# ASBB_Servo.net
KiCad netlist of a schematic drawn in Altium Designer
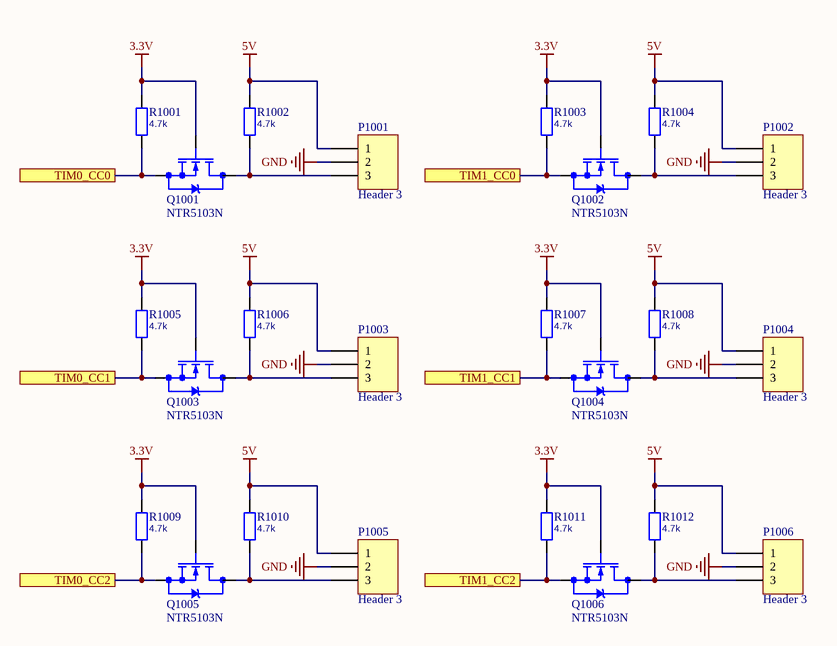
[diagram p0: ASBB_Servo.SchDoc]

(export (version "E")
  (design (tool "Eeschema 10.0.6"))
  (components
    (comp (ref "P1001")
      (value "Header 3")
      (footprint "HDR1X3")
      (description "Header, 3-Pin")
      (fields (field (name "PUBLISHER") "Altium Limited"))
      (libsource (lib "Miscellaneous Connectors") (part "Header 3"))
    )
    (comp (ref "P1002")
      (value "Header 3")
      (footprint "HDR1X3")
      (description "Header, 3-Pin")
      (fields (field (name "PUBLISHER") "Altium Limited"))
      (libsource (lib "Miscellaneous Connectors") (part "Header 3"))
    )
    (comp (ref "P1003")
      (value "Header 3")
      (footprint "HDR1X3")
      (description "Header, 3-Pin")
      (fields (field (name "PUBLISHER") "Altium Limited"))
      (libsource (lib "Miscellaneous Connectors") (part "Header 3"))
    )
    (comp (ref "P1004")
      (value "Header 3")
      (footprint "HDR1X3")
      (description "Header, 3-Pin")
      (fields (field (name "PUBLISHER") "Altium Limited"))
      (libsource (lib "Miscellaneous Connectors") (part "Header 3"))
    )
    (comp (ref "P1005")
      (value "Header 3")
      (footprint "HDR1X3")
      (description "Header, 3-Pin")
      (fields (field (name "PUBLISHER") "Altium Limited"))
      (libsource (lib "Miscellaneous Connectors") (part "Header 3"))
    )
    (comp (ref "P1006")
      (value "Header 3")
      (footprint "HDR1X3")
      (description "Header, 3-Pin")
      (fields (field (name "PUBLISHER") "Altium Limited"))
      (libsource (lib "Miscellaneous Connectors") (part "Header 3"))
    )
    (comp (ref "Q1001")
      (value "NTR5103N")
      (footprint "FZI:SOT23")
      (description "N-Channel MOSFET SOT23")
      (fields (field (name "PARTNUMBER") "?"))
      (libsource (lib "FZI") (part "NMOS SOT23"))
    )
    (comp (ref "Q1002")
      (value "NTR5103N")
      (footprint "FZI:SOT23")
      (description "N-Channel MOSFET SOT23")
      (fields (field (name "PARTNUMBER") "?"))
      (libsource (lib "FZI") (part "NMOS SOT23"))
    )
    (comp (ref "Q1003")
      (value "NTR5103N")
      (footprint "FZI:SOT23")
      (description "N-Channel MOSFET SOT23")
      (fields (field (name "PARTNUMBER") "?"))
      (libsource (lib "FZI") (part "NMOS SOT23"))
    )
    (comp (ref "Q1004")
      (value "NTR5103N")
      (footprint "FZI:SOT23")
      (description "N-Channel MOSFET SOT23")
      (fields (field (name "PARTNUMBER") "?"))
      (libsource (lib "FZI") (part "NMOS SOT23"))
    )
    (comp (ref "Q1005")
      (value "NTR5103N")
      (footprint "FZI:SOT23")
      (description "N-Channel MOSFET SOT23")
      (fields (field (name "PARTNUMBER") "?"))
      (libsource (lib "FZI") (part "NMOS SOT23"))
    )
    (comp (ref "Q1006")
      (value "NTR5103N")
      (footprint "FZI:SOT23")
      (description "N-Channel MOSFET SOT23")
      (fields (field (name "PARTNUMBER") "?"))
      (libsource (lib "FZI") (part "NMOS SOT23"))
    )
    (comp (ref "R1001")
      (value "4.7k")
      (footprint "0603")
      (description "Resistor")
      (fields (field (name "PARTNUMBER") "?"))
      (libsource (lib "FZI") (part "Resistor"))
    )
    (comp (ref "R1002")
      (value "4.7k")
      (footprint "0603")
      (description "Resistor")
      (fields (field (name "PARTNUMBER") "?"))
      (libsource (lib "FZI") (part "Resistor"))
    )
    (comp (ref "R1003")
      (value "4.7k")
      (footprint "0603")
      (description "Resistor")
      (fields (field (name "PARTNUMBER") "?"))
      (libsource (lib "FZI") (part "Resistor"))
    )
    (comp (ref "R1004")
      (value "4.7k")
      (footprint "0603")
      (description "Resistor")
      (fields (field (name "PARTNUMBER") "?"))
      (libsource (lib "FZI") (part "Resistor"))
    )
    (comp (ref "R1005")
      (value "4.7k")
      (footprint "0603")
      (description "Resistor")
      (fields (field (name "PARTNUMBER") "?"))
      (libsource (lib "FZI") (part "Resistor"))
    )
    (comp (ref "R1006")
      (value "4.7k")
      (footprint "0603")
      (description "Resistor")
      (fields (field (name "PARTNUMBER") "?"))
      (libsource (lib "FZI") (part "Resistor"))
    )
    (comp (ref "R1007")
      (value "4.7k")
      (footprint "0603")
      (description "Resistor")
      (fields (field (name "PARTNUMBER") "?"))
      (libsource (lib "FZI") (part "Resistor"))
    )
    (comp (ref "R1008")
      (value "4.7k")
      (footprint "0603")
      (description "Resistor")
      (fields (field (name "PARTNUMBER") "?"))
      (libsource (lib "FZI") (part "Resistor"))
    )
    (comp (ref "R1009")
      (value "4.7k")
      (footprint "0603")
      (description "Resistor")
      (fields (field (name "PARTNUMBER") "?"))
      (libsource (lib "FZI") (part "Resistor"))
    )
    (comp (ref "R1010")
      (value "4.7k")
      (footprint "0603")
      (description "Resistor")
      (fields (field (name "PARTNUMBER") "?"))
      (libsource (lib "FZI") (part "Resistor"))
    )
    (comp (ref "R1011")
      (value "4.7k")
      (footprint "0603")
      (description "Resistor")
      (fields (field (name "PARTNUMBER") "?"))
      (libsource (lib "FZI") (part "Resistor"))
    )
    (comp (ref "R1012")
      (value "4.7k")
      (footprint "0603")
      (description "Resistor")
      (fields (field (name "PARTNUMBER") "?"))
      (libsource (lib "FZI") (part "Resistor"))
    )
  )
  (nets
    (net (code "1") (name "/TIM0_CC0") (class "Default")
      (node (ref "Q1001") (pin "2") (pinfunction "S_2") (pintype "passive"))
      (node (ref "R1001") (pin "1") (pinfunction "1_1") (pintype "passive"))
    )
    (net (code "2") (name "/TIM0_CC1") (class "Default")
      (node (ref "Q1003") (pin "2") (pinfunction "S_2") (pintype "passive"))
      (node (ref "R1005") (pin "1") (pinfunction "1_1") (pintype "passive"))
    )
    (net (code "3") (name "/TIM0_CC2") (class "Default")
      (node (ref "Q1005") (pin "2") (pinfunction "S_2") (pintype "passive"))
      (node (ref "R1009") (pin "1") (pinfunction "1_1") (pintype "passive"))
    )
    (net (code "4") (name "/TIM1_CC0") (class "Default")
      (node (ref "Q1002") (pin "2") (pinfunction "S_2") (pintype "passive"))
      (node (ref "R1003") (pin "1") (pinfunction "1_1") (pintype "passive"))
    )
    (net (code "5") (name "/TIM1_CC1") (class "Default")
      (node (ref "Q1004") (pin "2") (pinfunction "S_2") (pintype "passive"))
      (node (ref "R1007") (pin "1") (pinfunction "1_1") (pintype "passive"))
    )
    (net (code "6") (name "/TIM1_CC2") (class "Default")
      (node (ref "Q1006") (pin "2") (pinfunction "S_2") (pintype "passive"))
      (node (ref "R1011") (pin "1") (pinfunction "1_1") (pintype "passive"))
    )
    (net (code "7") (name "3.3V") (class "Default")
      (node (ref "Q1001") (pin "1") (pinfunction "G_1") (pintype "passive"))
      (node (ref "Q1002") (pin "1") (pinfunction "G_1") (pintype "passive"))
      (node (ref "Q1003") (pin "1") (pinfunction "G_1") (pintype "passive"))
      (node (ref "Q1004") (pin "1") (pinfunction "G_1") (pintype "passive"))
      (node (ref "Q1005") (pin "1") (pinfunction "G_1") (pintype "passive"))
      (node (ref "Q1006") (pin "1") (pinfunction "G_1") (pintype "passive"))
      (node (ref "R1001") (pin "2") (pinfunction "2_2") (pintype "passive"))
      (node (ref "R1003") (pin "2") (pinfunction "2_2") (pintype "passive"))
      (node (ref "R1005") (pin "2") (pinfunction "2_2") (pintype "passive"))
      (node (ref "R1007") (pin "2") (pinfunction "2_2") (pintype "passive"))
      (node (ref "R1009") (pin "2") (pinfunction "2_2") (pintype "passive"))
      (node (ref "R1011") (pin "2") (pinfunction "2_2") (pintype "passive"))
    )
    (net (code "8") (name "5V") (class "Default")
      (node (ref "P1001") (pin "1") (pinfunction "1_1") (pintype "passive"))
      (node (ref "P1002") (pin "1") (pinfunction "1_1") (pintype "passive"))
      (node (ref "P1003") (pin "1") (pinfunction "1_1") (pintype "passive"))
      (node (ref "P1004") (pin "1") (pinfunction "1_1") (pintype "passive"))
      (node (ref "P1005") (pin "1") (pinfunction "1_1") (pintype "passive"))
      (node (ref "P1006") (pin "1") (pinfunction "1_1") (pintype "passive"))
      (node (ref "R1002") (pin "2") (pinfunction "2_2") (pintype "passive"))
      (node (ref "R1004") (pin "2") (pinfunction "2_2") (pintype "passive"))
      (node (ref "R1006") (pin "2") (pinfunction "2_2") (pintype "passive"))
      (node (ref "R1008") (pin "2") (pinfunction "2_2") (pintype "passive"))
      (node (ref "R1010") (pin "2") (pinfunction "2_2") (pintype "passive"))
      (node (ref "R1012") (pin "2") (pinfunction "2_2") (pintype "passive"))
    )
    (net (code "9") (name "GND") (class "Default")
      (node (ref "P1001") (pin "2") (pinfunction "2_2") (pintype "passive"))
      (node (ref "P1002") (pin "2") (pinfunction "2_2") (pintype "passive"))
      (node (ref "P1003") (pin "2") (pinfunction "2_2") (pintype "passive"))
      (node (ref "P1004") (pin "2") (pinfunction "2_2") (pintype "passive"))
      (node (ref "P1005") (pin "2") (pinfunction "2_2") (pintype "passive"))
      (node (ref "P1006") (pin "2") (pinfunction "2_2") (pintype "passive"))
    )
    (net (code "10") (name "Net-(Q1001-D)") (class "Default")
      (node (ref "P1001") (pin "3") (pinfunction "3_3") (pintype "passive"))
      (node (ref "Q1001") (pin "3") (pinfunction "D_3") (pintype "passive"))
      (node (ref "R1002") (pin "1") (pinfunction "1_1") (pintype "passive"))
    )
    (net (code "11") (name "Net-(Q1002-D)") (class "Default")
      (node (ref "P1002") (pin "3") (pinfunction "3_3") (pintype "passive"))
      (node (ref "Q1002") (pin "3") (pinfunction "D_3") (pintype "passive"))
      (node (ref "R1004") (pin "1") (pinfunction "1_1") (pintype "passive"))
    )
    (net (code "12") (name "Net-(Q1003-D)") (class "Default")
      (node (ref "P1003") (pin "3") (pinfunction "3_3") (pintype "passive"))
      (node (ref "Q1003") (pin "3") (pinfunction "D_3") (pintype "passive"))
      (node (ref "R1006") (pin "1") (pinfunction "1_1") (pintype "passive"))
    )
    (net (code "13") (name "Net-(Q1004-D)") (class "Default")
      (node (ref "P1004") (pin "3") (pinfunction "3_3") (pintype "passive"))
      (node (ref "Q1004") (pin "3") (pinfunction "D_3") (pintype "passive"))
      (node (ref "R1008") (pin "1") (pinfunction "1_1") (pintype "passive"))
    )
    (net (code "14") (name "Net-(Q1005-D)") (class "Default")
      (node (ref "P1005") (pin "3") (pinfunction "3_3") (pintype "passive"))
      (node (ref "Q1005") (pin "3") (pinfunction "D_3") (pintype "passive"))
      (node (ref "R1010") (pin "1") (pinfunction "1_1") (pintype "passive"))
    )
    (net (code "15") (name "Net-(Q1006-D)") (class "Default")
      (node (ref "P1006") (pin "3") (pinfunction "3_3") (pintype "passive"))
      (node (ref "Q1006") (pin "3") (pinfunction "D_3") (pintype "passive"))
      (node (ref "R1012") (pin "1") (pinfunction "1_1") (pintype "passive"))
    )
  )
)
